# MCU103A_AltRouting_Misc.net
KiCad netlist of a schematic drawn in Altium Designer
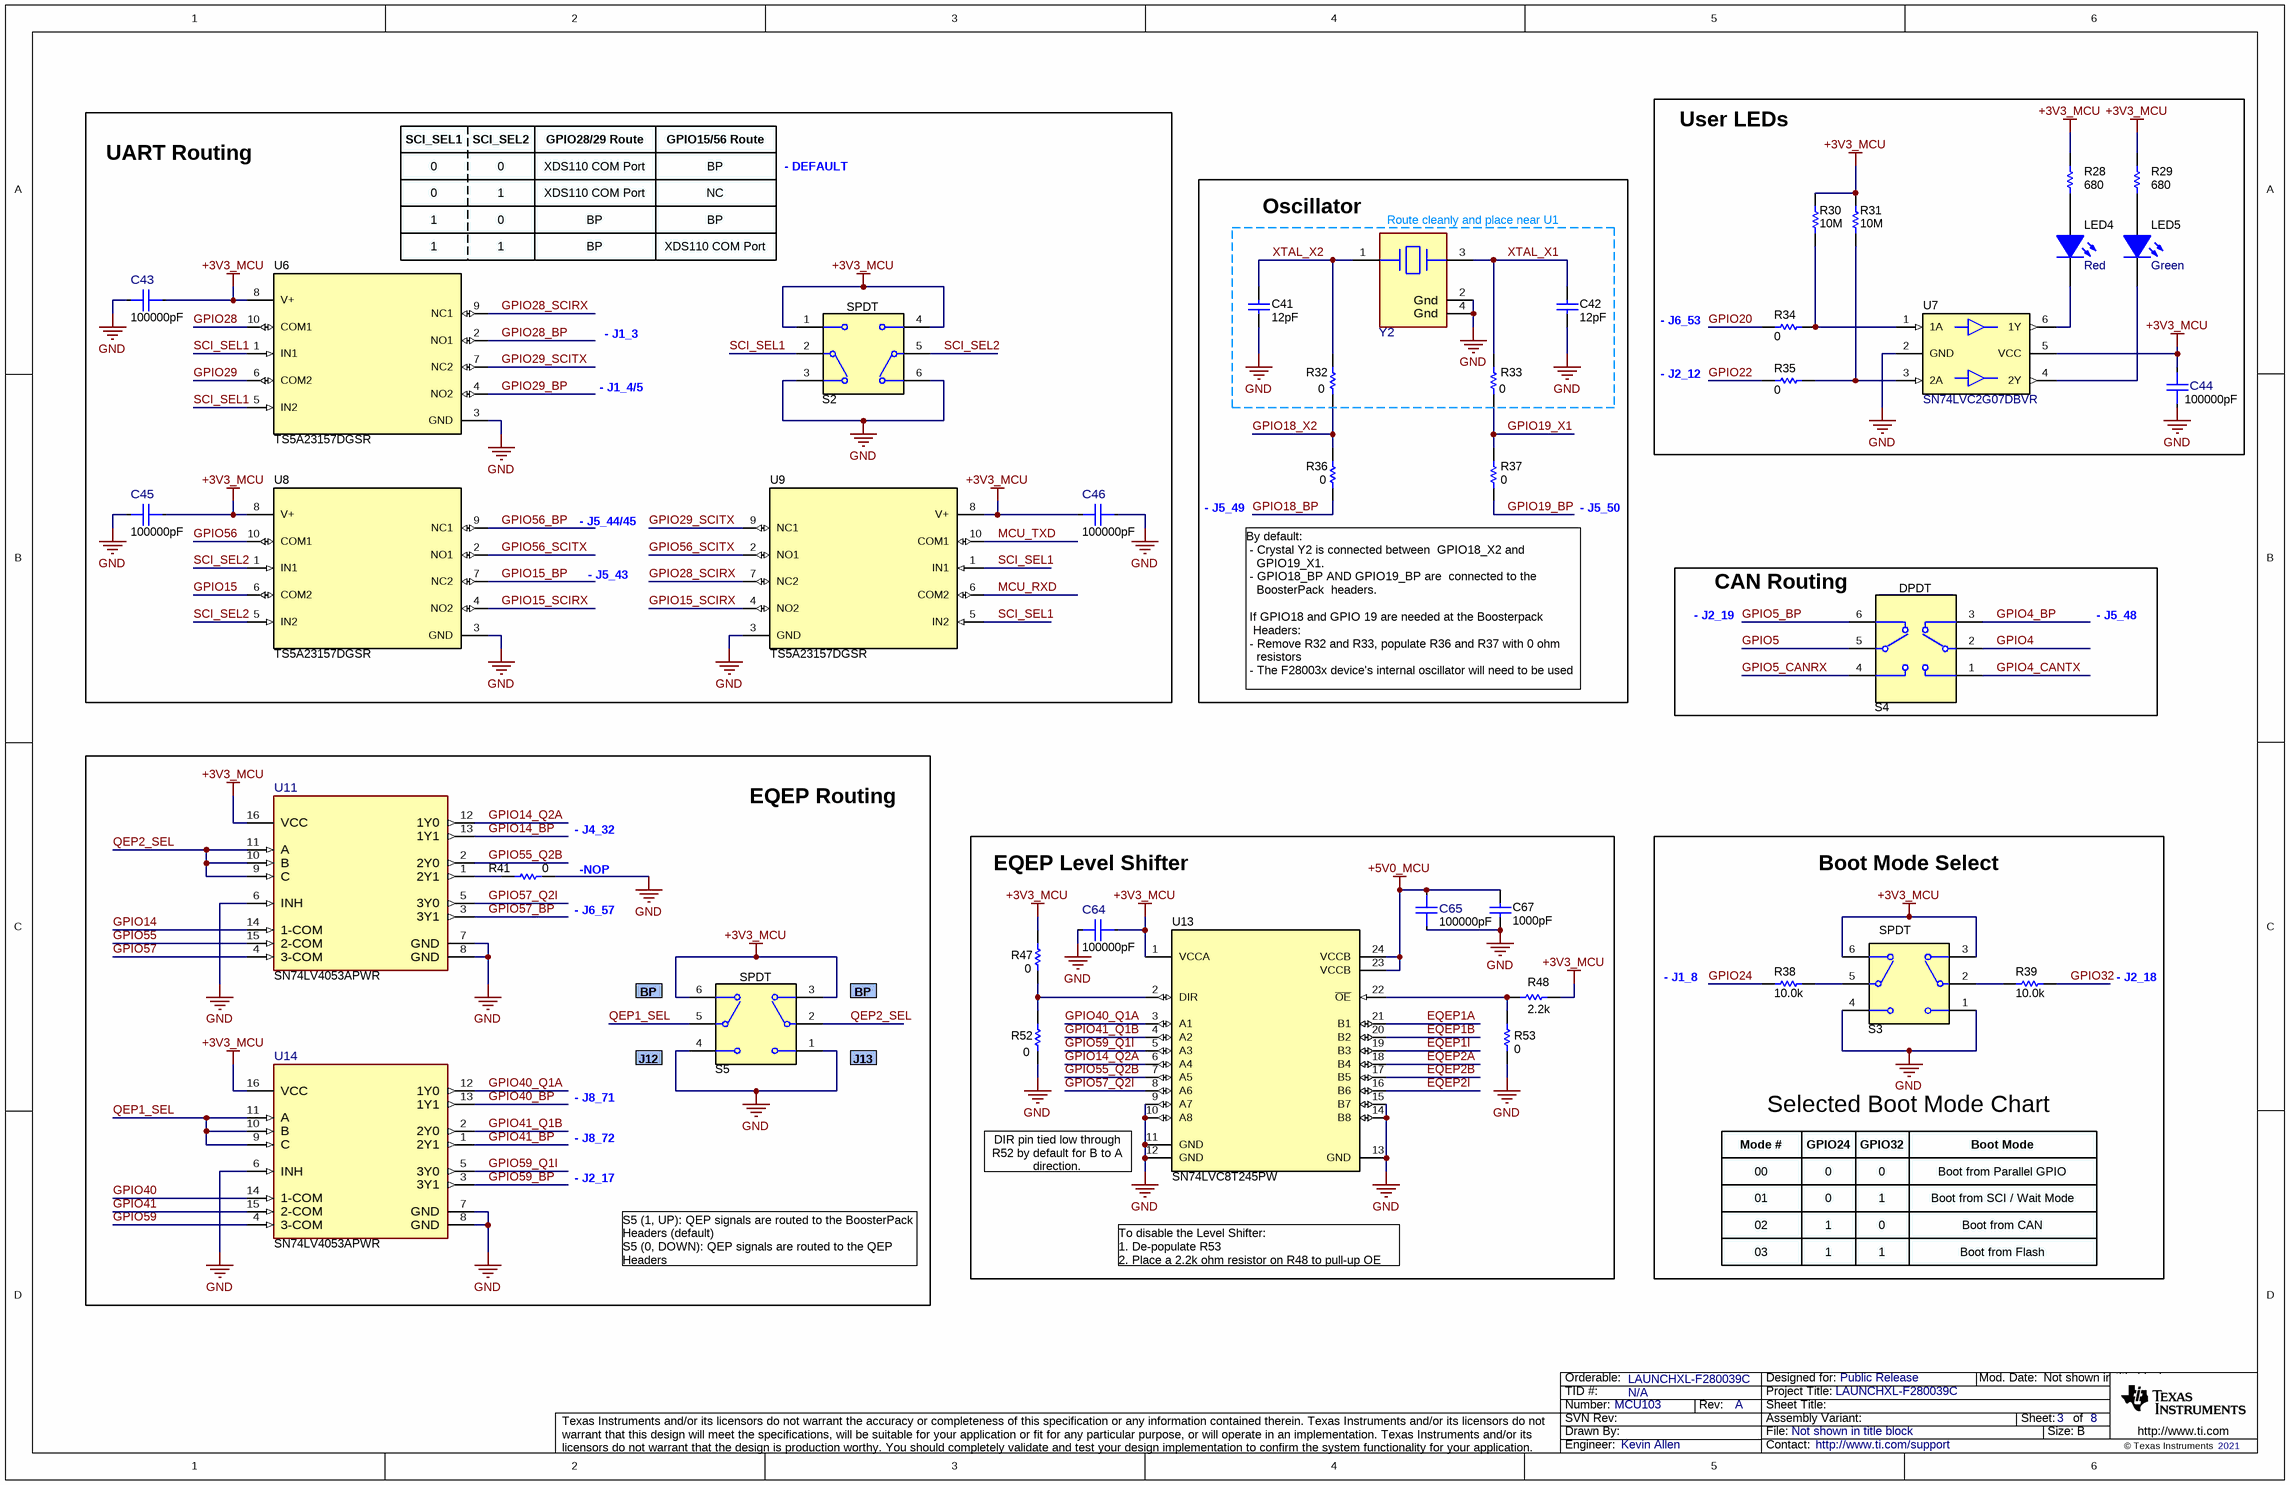
[diagram p0: MCU103A_AltRouting_Misc.SchDoc]

(export (version "E")
  (design (tool "Eeschema 10.0.6"))
  (components
    (comp (ref "C41")
      (value "C0402C120J3GACAUTO")
      (footprint "0402")
      (description "CAP, CERM, 12 pF, 25 V, +/- 5%, C0G/NP0, AEC-Q200 Grade 1, 0402")
      (fields
        (field (name "MANUFACTURER") "Kemet")
        (field (name "VALUEDISPLAYED") "12pF")
        (field (name "PUBLISHER") "Texas Instruments")
      )
      (libsource (lib "Altium Vault - TI") (part "Capacitor"))
    )
    (comp (ref "C42")
      (value "C0402C120J3GACAUTO")
      (footprint "0402")
      (description "CAP, CERM, 12 pF, 25 V, +/- 5%, C0G/NP0, AEC-Q200 Grade 1, 0402")
      (fields
        (field (name "MANUFACTURER") "Kemet")
        (field (name "VALUEDISPLAYED") "12pF")
        (field (name "PUBLISHER") "Texas Instruments")
      )
      (libsource (lib "Altium Vault - TI") (part "Capacitor"))
    )
    (comp (ref "C43")
      (value "885012205018")
      (footprint "FP-885012205018_0402-MFG")
      (description "0.1µF ±10% 10V Ceramic Capacitor X7R 0402 (1005 Metric)")
      (fields
        (field (name "MANUFACTURER") "Wurth Electronics")
        (field (name "MOUSER PART NUMBER") "710-885012205018")
        (field (name "VALUEDISPLAYED") "100000pF")
      )
      (libsource (lib "Altium Vault - TI") (part "SYM-885012205018"))
    )
    (comp (ref "C44")
      (value "885012205018")
      (footprint "FP-885012205018_0402-MFG")
      (description "0.1µF ±10% 10V Ceramic Capacitor X7R 0402 (1005 Metric)")
      (fields
        (field (name "MANUFACTURER") "Wurth Electronics")
        (field (name "MOUSER PART NUMBER") "710-885012205018")
        (field (name "VALUEDISPLAYED") "100000pF")
      )
      (libsource (lib "Altium Vault - TI") (part "SYM-885012205018"))
    )
    (comp (ref "C45")
      (value "885012205018")
      (footprint "FP-885012205018_0402-MFG")
      (description "0.1µF ±10% 10V Ceramic Capacitor X7R 0402 (1005 Metric)")
      (fields
        (field (name "MANUFACTURER") "Wurth Electronics")
        (field (name "MOUSER PART NUMBER") "710-885012205018")
        (field (name "VALUEDISPLAYED") "100000pF")
      )
      (libsource (lib "Altium Vault - TI") (part "SYM-885012205018"))
    )
    (comp (ref "C46")
      (value "885012205018")
      (footprint "FP-885012205018_0402-MFG")
      (description "0.1µF ±10% 10V Ceramic Capacitor X7R 0402 (1005 Metric)")
      (fields
        (field (name "MANUFACTURER") "Wurth Electronics")
        (field (name "MOUSER PART NUMBER") "710-885012205018")
        (field (name "VALUEDISPLAYED") "100000pF")
      )
      (libsource (lib "Altium Vault - TI") (part "SYM-885012205018"))
    )
    (comp (ref "C64")
      (value "885012205018")
      (footprint "FP-885012205018_0402-MFG")
      (description "0.1µF ±10% 10V Ceramic Capacitor X7R 0402 (1005 Metric)")
      (fields
        (field (name "MANUFACTURER") "Wurth Electronics")
        (field (name "MOUSER PART NUMBER") "710-885012205018")
        (field (name "VALUEDISPLAYED") "100000pF")
      )
      (libsource (lib "Altium Vault - TI") (part "SYM-885012205018"))
    )
    (comp (ref "C65")
      (value "885012205018")
      (footprint "FP-885012205018_0402-MFG")
      (description "0.1µF ±10% 10V Ceramic Capacitor X7R 0402 (1005 Metric)")
      (fields
        (field (name "MANUFACTURER") "Wurth Electronics")
        (field (name "MOUSER PART NUMBER") "710-885012205018")
        (field (name "VALUEDISPLAYED") "100000pF")
      )
      (libsource (lib "Altium Vault - TI") (part "SYM-885012205018"))
    )
    (comp (ref "C67")
      (value "885012205061")
      (footprint "0402")
      (description "CAP, CERM, 1000 pF, 50 V, +/- 10%, X7R, 0402")
      (fields
        (field (name "VALUEDISPLAYED") "1000pF")
        (field (name "MANUFACTURER") "Wurth Elektronik")
        (field (name "PUBLISHER") "Texas Instruments")
      )
      (libsource (lib "Altium Vault - TI") (part "Capacitor"))
    )
    (comp (ref "LED4")
      (value "Red")
      (footprint "WL-SMCW_RED_0805")
      (description "LED, Red, SMD")
      (fields (field (name "MANUFACTURER") "Wurth Elektronik") (field (name "PARTNUMBER") "150080SS75000"))
      (libsource (lib "Altium Vault - TI") (part "LED_A2_K1"))
    )
    (comp (ref "LED5")
      (value "Green")
      (footprint "LED_LTST-C171")
      (description "LED, Green, SMD")
      (fields (field (name "MANUFACTURER") "Lite-On") (field (name "PARTNUMBER") "LTST-C171GKT"))
      (libsource (lib "Altium Vault - TI") (part "LED"))
    )
    (comp (ref "R28")
      (value "CRCW0402680RJNED")
      (footprint "0402")
      (description "RES, 680, 5%, 0.063 W, AEC-Q200 Grade 0, 0402")
      (fields (field (name "MANUFACTURER") "Vishay-Dale") (field (name "VALUEDISPLAYED") "680"))
      (libsource (lib "Altium Vault - TI") (part "Resistor"))
    )
    (comp (ref "R29")
      (value "CRCW0402680RJNED")
      (footprint "0402")
      (description "RES, 680, 5%, 0.063 W, AEC-Q200 Grade 0, 0402")
      (fields (field (name "MANUFACTURER") "Vishay-Dale") (field (name "VALUEDISPLAYED") "680"))
      (libsource (lib "Altium Vault - TI") (part "Resistor"))
    )
    (comp (ref "R30")
      (value "CRCW040210M0JNED")
      (footprint "0402")
      (description "RES, 10 M, 5%, 0.063 W, AEC-Q200 Grade 0, 0402")
      (fields (field (name "VALUEDISPLAYED") "10M") (field (name "MANUFACTURER") "Vishay-Dale"))
      (libsource (lib "Altium Vault - TI") (part "Resistor"))
    )
    (comp (ref "R31")
      (value "CRCW040210M0JNED")
      (footprint "0402")
      (description "RES, 10 M, 5%, 0.063 W, AEC-Q200 Grade 0, 0402")
      (fields (field (name "VALUEDISPLAYED") "10M") (field (name "MANUFACTURER") "Vishay-Dale"))
      (libsource (lib "Altium Vault - TI") (part "Resistor"))
    )
    (comp (ref "R32")
      (value "CRCW06030000Z0EA")
      (footprint "0603")
      (description "RES, 0, 5%, 0.1 W, AEC-Q200 Grade 0, 0603")
      (fields (field (name "VALUEDISPLAYED") "0") (field (name "MANUFACTURER") "Vishay-Dale"))
      (libsource (lib "Altium Vault - TI") (part "Resistor"))
    )
    (comp (ref "R33")
      (value "CRCW06030000Z0EA")
      (footprint "0603")
      (description "RES, 0, 5%, 0.1 W, AEC-Q200 Grade 0, 0603")
      (fields (field (name "VALUEDISPLAYED") "0") (field (name "MANUFACTURER") "Vishay-Dale"))
      (libsource (lib "Altium Vault - TI") (part "Resistor"))
    )
    (comp (ref "R34")
      (value "CRCW06030000Z0EA")
      (footprint "0603")
      (description "RES, 0, 5%, 0.1 W, AEC-Q200 Grade 0, 0603")
      (fields (field (name "VALUEDISPLAYED") "0") (field (name "MANUFACTURER") "Vishay-Dale"))
      (libsource (lib "Altium Vault - TI") (part "Resistor"))
    )
    (comp (ref "R35")
      (value "CRCW06030000Z0EA")
      (footprint "0603")
      (description "RES, 0, 5%, 0.1 W, AEC-Q200 Grade 0, 0603")
      (fields (field (name "VALUEDISPLAYED") "0") (field (name "MANUFACTURER") "Vishay-Dale"))
      (libsource (lib "Altium Vault - TI") (part "Resistor"))
    )
    (comp (ref "R36")
      (value "CRCW06030000Z0EA")
      (footprint "0603")
      (description "RES, 0, 5%, 0.1 W, AEC-Q200 Grade 0, 0603")
      (fields (field (name "VALUEDISPLAYED") "0") (field (name "MANUFACTURER") "Vishay-Dale"))
      (libsource (lib "") (part "Resistor_1"))
    )
    (comp (ref "R37")
      (value "CRCW06030000Z0EA")
      (footprint "0603")
      (description "RES, 0, 5%, 0.1 W, AEC-Q200 Grade 0, 0603")
      (fields (field (name "VALUEDISPLAYED") "0") (field (name "MANUFACTURER") "Vishay-Dale"))
      (libsource (lib "Altium Vault - TI") (part "Resistor"))
    )
    (comp (ref "R38")
      (value "RC0603FR-0710KL")
      (footprint "0603")
      (description "RES, 10.0 k, 1%, 0.1 W, 0603")
      (fields (field (name "MANUFACTURER") "Yageo") (field (name "VALUEDISPLAYED") "10.0k"))
      (libsource (lib "Altium Vault - TI") (part "Resistor"))
    )
    (comp (ref "R39")
      (value "RC0603FR-0710KL")
      (footprint "0603")
      (description "RES, 10.0 k, 1%, 0.1 W, 0603")
      (fields (field (name "MANUFACTURER") "Yageo") (field (name "VALUEDISPLAYED") "10.0k"))
      (libsource (lib "Altium Vault - TI") (part "Resistor"))
    )
    (comp (ref "R41")
      (value "CRCW06030000Z0EA")
      (footprint "0603")
      (description "RES, 0, 5%, 0.1 W, AEC-Q200 Grade 0, 0603")
      (fields (field (name "VALUEDISPLAYED") "0") (field (name "MANUFACTURER") "Vishay-Dale"))
      (libsource (lib "Altium Vault - TI") (part "Resistor"))
    )
    (comp (ref "R47")
      (value "CRCW06030000Z0EA")
      (footprint "0603")
      (description "RES, 0, 5%, 0.1 W, AEC-Q200 Grade 0, 0603")
      (fields (field (name "VALUEDISPLAYED") "0") (field (name "MANUFACTURER") "Vishay-Dale"))
      (libsource (lib "Altium Vault - TI") (part "Resistor"))
    )
    (comp (ref "R48")
      (value "CRCW06032K20JNEA")
      (footprint "0603")
      (description "RES, 2.2 k, 5%, 0.1 W, AEC-Q200 Grade 0, 0603")
      (fields (field (name "VALUEDISPLAYED") "2.2k") (field (name "MANUFACTURER") "Vishay-Dale"))
      (libsource (lib "Altium Vault - TI") (part "Resistor"))
    )
    (comp (ref "R52")
      (value "CRCW06030000Z0EA")
      (footprint "0603")
      (description "RES, 0, 5%, 0.1 W, AEC-Q200 Grade 0, 0603")
      (fields (field (name "VALUEDISPLAYED") "0") (field (name "MANUFACTURER") "Vishay-Dale"))
      (libsource (lib "Altium Vault - TI") (part "Resistor"))
    )
    (comp (ref "R53")
      (value "CRCW06030000Z0EA")
      (footprint "0603")
      (description "RES, 0, 5%, 0.1 W, AEC-Q200 Grade 0, 0603")
      (fields (field (name "VALUEDISPLAYED") "0") (field (name "MANUFACTURER") "Vishay-Dale"))
      (libsource (lib "Altium Vault - TI") (part "Resistor"))
    )
    (comp (ref "S2")
      (value "CAS-D20TA")
      (footprint "SW_CAS-D20TA")
      (description "Switch, Dual SPDT,  2 Pos, 0.1A, 6VDC, SMD")
      (fields
        (field (name "MANUFACTURER") "Copal Electronics")
        (field (name "PUBLISHER") "Texas Instruments")
      )
      (libsource (lib "") (part "SW_SPDT_CAS-D20TA_1"))
    )
    (comp (ref "S3")
      (value "CAS-D20TA")
      (footprint "SW_CAS-D20TA")
      (description "Switch, Dual SPDT,  2 Pos, 0.1A, 6VDC, SMD")
      (fields
        (field (name "MANUFACTURER") "Copal Electronics")
        (field (name "PUBLISHER") "Texas Instruments")
      )
      (libsource (lib "Altium Vault - TI") (part "SW_SPDT_CAS-D20TA"))
    )
    (comp (ref "S4")
      (value "CAS-220TA")
      (footprint "SW_CAS-220TA")
      (description "SLIDE SWITCH DPDT  .1A, SMT")
      (fields
        (field (name "MANUFACTURER") "Copal Electronics")
        (field (name "PUBLISHER") "Texas Instruments")
      )
      (libsource (lib "Altium Vault - TI") (part "SW_CAS-220TA"))
    )
    (comp (ref "S5")
      (value "CAS-D20TA")
      (footprint "SW_CAS-D20TA")
      (description "Switch, Dual SPDT,  2 Pos, 0.1A, 6VDC, SMD")
      (fields
        (field (name "MANUFACTURER") "Copal Electronics")
        (field (name "PUBLISHER") "Texas Instruments")
      )
      (libsource (lib "Altium Vault - TI") (part "SW_SPDT_CAS-D20TA"))
    )
    (comp (ref "U6")
      (value "TS5A23157DGSR")
      (footprint "DGS0010A_N")
      (description "DUAL 10-Ohm SPDT ANALOG SWITCH, DGS0010A (VSSOP-10)")
      (fields
        (field (name "ALTERNATE PARTNUMBER") "TS5A23157DGST")
        (field (name "MANUFACTURER") "Texas Instruments")
        (field (name "PARTNUMBER") "TS5A23157DGSR")
        (field (name "PUBLISHER") "Texas Instruments")
      )
      (libsource (lib "Altium Vault - TI") (part "TS5A23159"))
    )
    (comp (ref "U7")
      (value "SN74LVC2G07DBVR")
      (footprint "DBV0006A_N")
      (description "Dual Buffer/Driver with Open-Drain Output, DBV0006A, LARGE T&R")
      (fields
        (field (name "GENERIC PART NUMBER") "SN74LVC2G07")
        (field (name "MANUFACTURER") "Texas Instruments")
      )
      (libsource (lib "Altium Vault - TI") (part "SN74LVC2G07"))
    )
    (comp (ref "U8")
      (value "TS5A23157DGSR")
      (footprint "DGS0010A_N")
      (description "DUAL 10-Ohm SPDT ANALOG SWITCH, DGS0010A (VSSOP-10)")
      (fields
        (field (name "ALTERNATE PARTNUMBER") "TS5A23157DGST")
        (field (name "MANUFACTURER") "Texas Instruments")
        (field (name "PARTNUMBER") "TS5A23157DGSR")
        (field (name "PUBLISHER") "Texas Instruments")
      )
      (libsource (lib "Altium Vault - TI") (part "TS5A23159"))
    )
    (comp (ref "U9")
      (value "TS5A23157DGSR")
      (footprint "DGS0010A_N")
      (description "DUAL 10-Ohm SPDT ANALOG SWITCH, DGS0010A (VSSOP-10)")
      (fields
        (field (name "ALTERNATE PARTNUMBER") "TS5A23157DGST")
        (field (name "MANUFACTURER") "Texas Instruments")
        (field (name "PARTNUMBER") "TS5A23157DGSR")
        (field (name "PUBLISHER") "Texas Instruments")
      )
      (libsource (lib "") (part "TS5A23159_1"))
    )
    (comp (ref "U11")
      (value "SN74LV4053APWR")
      (footprint "PW0016A-MFG")
      (description "3 Circuit IC Switch 2:1 75Ohm 16-TSSOP")
      (fields
        (field (name "PARTNUMBER") "SN74LV4053APWR")
        (field (name "MOUSER PART NUMBER") "595-SN74LV4053APWR")
        (field (name "DIGIKEY PART NUMBER") "296-3833-1-ND")
      )
      (libsource (lib "Altium Vault - TI") (part "SYM-SN74LV4053APWR"))
    )
    (comp (ref "U13")
      (value "SN74LVC8T245PW")
      (footprint "PW0024A_N")
      (fields (field (name "MANUFACTURER") "Texas Instruments") (field (name "PARTNUMBER") "SN74LVC8T245PW"))
      (libsource (lib "Altium Vault - TI") (part "SN74LVC8T245"))
    )
    (comp (ref "U14")
      (value "SN74LV4053APWR")
      (footprint "PW0016A-MFG")
      (description "3 Circuit IC Switch 2:1 75Ohm 16-TSSOP")
      (fields
        (field (name "PARTNUMBER") "SN74LV4053APWR")
        (field (name "MOUSER PART NUMBER") "595-SN74LV4053APWR")
        (field (name "DIGIKEY PART NUMBER") "296-3833-1-ND")
      )
      (libsource (lib "Altium Vault - TI") (part "SYM-SN74LV4053APWR"))
    )
    (comp (ref "Y2")
      (value "ECS-200-8-30B-CKM")
      (footprint "FP-ECS-200-8-30B-CKM_SMD4-MFG")
      (description "20 MHz ±10ppm Crystal 8pF 40 Ohms 4-SMD, No Lead")
      (fields
        (field (name "MOUSER PART NUMBER") "520-200-8-30B-CKM")
        (field (name "MANUFACTURER") "ECS International")
      )
      (libsource (lib "Altium Vault - TI") (part "SYM-ECS-200-8-30B-CKM"))
    )
  )
  (nets
    (net (code "1") (name "+3V3_MCU") (class "Default")
      (node (ref "C43") (pin "1") (pinfunction "1_1") (pintype "passive"))
      (node (ref "C44") (pin "2") (pinfunction "2_2") (pintype "passive"))
      (node (ref "C45") (pin "1") (pinfunction "1_1") (pintype "passive"))
      (node (ref "C46") (pin "2") (pinfunction "2_2") (pintype "passive"))
      (node (ref "C64") (pin "1") (pinfunction "1_1") (pintype "passive"))
      (node (ref "R28") (pin "2") (pinfunction "2_2") (pintype "passive"))
      (node (ref "R29") (pin "2") (pinfunction "2_2") (pintype "passive"))
      (node (ref "R30") (pin "2") (pinfunction "2_2") (pintype "passive"))
      (node (ref "R31") (pin "2") (pinfunction "2_2") (pintype "passive"))
      (node (ref "R47") (pin "2") (pinfunction "2_2") (pintype "passive"))
      (node (ref "R48") (pin "2") (pinfunction "2_2") (pintype "passive"))
      (node (ref "S2") (pin "1") (pinfunction "1_1") (pintype "passive"))
      (node (ref "S2") (pin "4") (pinfunction "4_4") (pintype "passive"))
      (node (ref "S3") (pin "3") (pinfunction "3_3") (pintype "passive"))
      (node (ref "S3") (pin "6") (pinfunction "6_6") (pintype "passive"))
      (node (ref "S5") (pin "3") (pinfunction "3_3") (pintype "passive"))
      (node (ref "S5") (pin "6") (pinfunction "6_6") (pintype "passive"))
      (node (ref "U11") (pin "16") (pinfunction "VCC_16") (pintype "power_in"))
      (node (ref "U13") (pin "1") (pinfunction "VCCA_1") (pintype "power_in"))
      (node (ref "U14") (pin "16") (pinfunction "VCC_16") (pintype "power_in"))
      (node (ref "U6") (pin "8") (pinfunction "V+_8") (pintype "power_in"))
      (node (ref "U7") (pin "5") (pinfunction "VCC_5") (pintype "power_in"))
      (node (ref "U8") (pin "8") (pinfunction "V+_8") (pintype "power_in"))
      (node (ref "U9") (pin "8") (pinfunction "V+_8") (pintype "power_in"))
    )
    (net (code "2") (name "+5V0_MCU") (class "Default")
      (node (ref "C65") (pin "2") (pinfunction "2_2") (pintype "passive"))
      (node (ref "C67") (pin "1") (pinfunction "1_1") (pintype "passive"))
      (node (ref "U13") (pin "23") (pinfunction "VCCB_23") (pintype "power_in"))
      (node (ref "U13") (pin "24") (pinfunction "VCCB_24") (pintype "power_in"))
    )
    (net (code "3") (name "/EQEP1A") (class "Default")
      (node (ref "U13") (pin "21") (pinfunction "B1_21") (pintype "bidirectional"))
    )
    (net (code "4") (name "/EQEP1B") (class "Default")
      (node (ref "U13") (pin "20") (pinfunction "B2_20") (pintype "bidirectional"))
    )
    (net (code "5") (name "/EQEP1I") (class "Default")
      (node (ref "U13") (pin "19") (pinfunction "B3_19") (pintype "bidirectional"))
    )
    (net (code "6") (name "/EQEP2A") (class "Default")
      (node (ref "U13") (pin "18") (pinfunction "B4_18") (pintype "bidirectional"))
    )
    (net (code "7") (name "/EQEP2B") (class "Default")
      (node (ref "U13") (pin "17") (pinfunction "B5_17") (pintype "bidirectional"))
    )
    (net (code "8") (name "/EQEP2I") (class "Default")
      (node (ref "U13") (pin "16") (pinfunction "B6_16") (pintype "bidirectional"))
    )
    (net (code "9") (name "/GPIO4") (class "Default")
      (node (ref "S4") (pin "2") (pinfunction "2_2") (pintype "passive"))
    )
    (net (code "10") (name "/GPIO4_BP") (class "Default")
      (node (ref "S4") (pin "3") (pinfunction "3_3") (pintype "passive"))
    )
    (net (code "11") (name "/GPIO4_CANTX") (class "Default")
      (node (ref "S4") (pin "1") (pinfunction "1_1") (pintype "passive"))
    )
    (net (code "12") (name "/GPIO5") (class "Default")
      (node (ref "S4") (pin "5") (pinfunction "5_5") (pintype "passive"))
    )
    (net (code "13") (name "/GPIO5_BP") (class "Default")
      (node (ref "S4") (pin "6") (pinfunction "6_6") (pintype "passive"))
    )
    (net (code "14") (name "/GPIO5_CANRX") (class "Default")
      (node (ref "S4") (pin "4") (pinfunction "4_4") (pintype "passive"))
    )
    (net (code "15") (name "/GPIO14") (class "Default")
      (node (ref "U11") (pin "14") (pinfunction "1-COM_14") (pintype "input"))
    )
    (net (code "16") (name "/GPIO14_BP") (class "Default")
      (node (ref "U11") (pin "13") (pinfunction "1Y1_13") (pintype "output"))
    )
    (net (code "17") (name "/GPIO14_Q2A") (class "Default")
      (node (ref "U11") (pin "12") (pinfunction "1Y0_12") (pintype "output"))
      (node (ref "U13") (pin "6") (pinfunction "A4_6") (pintype "bidirectional"))
    )
    (net (code "18") (name "/GPIO15") (class "Default")
      (node (ref "U8") (pin "6") (pinfunction "COM2_6") (pintype "bidirectional"))
    )
    (net (code "19") (name "/GPIO15_BP") (class "Default")
      (node (ref "U8") (pin "7") (pinfunction "NC2_7") (pintype "bidirectional"))
    )
    (net (code "20") (name "/GPIO15_SCIRX") (class "Default")
      (node (ref "U8") (pin "4") (pinfunction "NO2_4") (pintype "bidirectional"))
      (node (ref "U9") (pin "4") (pinfunction "NO2_4") (pintype "bidirectional"))
    )
    (net (code "21") (name "/GPIO18_BP") (class "Default")
      (node (ref "R36") (pin "1") (pinfunction "1_1") (pintype "passive"))
    )
    (net (code "22") (name "/GPIO18_X2") (class "Default")
      (node (ref "R32") (pin "1") (pinfunction "1_1") (pintype "passive"))
      (node (ref "R36") (pin "2") (pinfunction "2_2") (pintype "passive"))
    )
    (net (code "23") (name "/GPIO19_BP") (class "Default")
      (node (ref "R37") (pin "1") (pinfunction "1_1") (pintype "passive"))
    )
    (net (code "24") (name "/GPIO19_X1") (class "Default")
      (node (ref "R33") (pin "1") (pinfunction "1_1") (pintype "passive"))
      (node (ref "R37") (pin "2") (pinfunction "2_2") (pintype "passive"))
    )
    (net (code "25") (name "/GPIO20") (class "Default")
      (node (ref "R34") (pin "1") (pinfunction "1_1") (pintype "passive"))
    )
    (net (code "26") (name "/GPIO22") (class "Default")
      (node (ref "R35") (pin "1") (pinfunction "1_1") (pintype "passive"))
    )
    (net (code "27") (name "/GPIO24") (class "Default")
      (node (ref "R38") (pin "1") (pinfunction "1_1") (pintype "passive"))
    )
    (net (code "28") (name "/GPIO28") (class "Default")
      (node (ref "U6") (pin "10") (pinfunction "COM1_10") (pintype "bidirectional"))
    )
    (net (code "29") (name "/GPIO28_BP") (class "Default")
      (node (ref "U6") (pin "2") (pinfunction "NO1_2") (pintype "bidirectional"))
    )
    (net (code "30") (name "/GPIO28_SCIRX") (class "Default")
      (node (ref "U6") (pin "9") (pinfunction "NC1_9") (pintype "bidirectional"))
      (node (ref "U9") (pin "7") (pinfunction "NC2_7") (pintype "bidirectional"))
    )
    (net (code "31") (name "/GPIO29") (class "Default")
      (node (ref "U6") (pin "6") (pinfunction "COM2_6") (pintype "bidirectional"))
    )
    (net (code "32") (name "/GPIO29_BP") (class "Default")
      (node (ref "U6") (pin "4") (pinfunction "NO2_4") (pintype "bidirectional"))
    )
    (net (code "33") (name "/GPIO29_SCITX") (class "Default")
      (node (ref "U6") (pin "7") (pinfunction "NC2_7") (pintype "bidirectional"))
      (node (ref "U9") (pin "9") (pinfunction "NC1_9") (pintype "bidirectional"))
    )
    (net (code "34") (name "/GPIO32") (class "Default")
      (node (ref "R39") (pin "2") (pinfunction "2_2") (pintype "passive"))
    )
    (net (code "35") (name "/GPIO40") (class "Default")
      (node (ref "U14") (pin "14") (pinfunction "1-COM_14") (pintype "input"))
    )
    (net (code "36") (name "/GPIO40_BP") (class "Default")
      (node (ref "U14") (pin "13") (pinfunction "1Y1_13") (pintype "output"))
    )
    (net (code "37") (name "/GPIO40_Q1A") (class "Default")
      (node (ref "U13") (pin "3") (pinfunction "A1_3") (pintype "bidirectional"))
      (node (ref "U14") (pin "12") (pinfunction "1Y0_12") (pintype "output"))
    )
    (net (code "38") (name "/GPIO41") (class "Default")
      (node (ref "U14") (pin "15") (pinfunction "2-COM_15") (pintype "input"))
    )
    (net (code "39") (name "/GPIO41_BP") (class "Default")
      (node (ref "U14") (pin "1") (pinfunction "2Y1_1") (pintype "output"))
    )
    (net (code "40") (name "/GPIO41_Q1B") (class "Default")
      (node (ref "U13") (pin "4") (pinfunction "A2_4") (pintype "bidirectional"))
      (node (ref "U14") (pin "2") (pinfunction "2Y0_2") (pintype "output"))
    )
    (net (code "41") (name "/GPIO55") (class "Default")
      (node (ref "U11") (pin "15") (pinfunction "2-COM_15") (pintype "input"))
    )
    (net (code "42") (name "/GPIO55_Q2B") (class "Default")
      (node (ref "U11") (pin "2") (pinfunction "2Y0_2") (pintype "output"))
      (node (ref "U13") (pin "7") (pinfunction "A5_7") (pintype "bidirectional"))
    )
    (net (code "43") (name "/GPIO56") (class "Default")
      (node (ref "U8") (pin "10") (pinfunction "COM1_10") (pintype "bidirectional"))
    )
    (net (code "44") (name "/GPIO56_BP") (class "Default")
      (node (ref "U8") (pin "9") (pinfunction "NC1_9") (pintype "bidirectional"))
    )
    (net (code "45") (name "/GPIO56_SCITX") (class "Default")
      (node (ref "U8") (pin "2") (pinfunction "NO1_2") (pintype "bidirectional"))
      (node (ref "U9") (pin "2") (pinfunction "NO1_2") (pintype "bidirectional"))
    )
    (net (code "46") (name "/GPIO57") (class "Default")
      (node (ref "U11") (pin "4") (pinfunction "3-COM_4") (pintype "input"))
    )
    (net (code "47") (name "/GPIO57_BP") (class "Default")
      (node (ref "U11") (pin "3") (pinfunction "3Y1_3") (pintype "output"))
    )
    (net (code "48") (name "/GPIO57_Q2I") (class "Default")
      (node (ref "U11") (pin "5") (pinfunction "3Y0_5") (pintype "output"))
      (node (ref "U13") (pin "8") (pinfunction "A6_8") (pintype "bidirectional"))
    )
    (net (code "49") (name "/GPIO59") (class "Default")
      (node (ref "U14") (pin "4") (pinfunction "3-COM_4") (pintype "input"))
    )
    (net (code "50") (name "/GPIO59_BP") (class "Default")
      (node (ref "U14") (pin "3") (pinfunction "3Y1_3") (pintype "output"))
    )
    (net (code "51") (name "/GPIO59_Q1I") (class "Default")
      (node (ref "U13") (pin "5") (pinfunction "A3_5") (pintype "bidirectional"))
      (node (ref "U14") (pin "5") (pinfunction "3Y0_5") (pintype "output"))
    )
    (net (code "52") (name "/MCU_RXD") (class "Default")
      (node (ref "U9") (pin "6") (pinfunction "COM2_6") (pintype "bidirectional"))
    )
    (net (code "53") (name "/MCU_TXD") (class "Default")
      (node (ref "U9") (pin "10") (pinfunction "COM1_10") (pintype "bidirectional"))
    )
    (net (code "54") (name "/QEP1_SEL") (class "Default")
      (node (ref "S5") (pin "5") (pinfunction "C_5") (pintype "passive"))
      (node (ref "U14") (pin "10") (pinfunction "B_10") (pintype "input"))
      (node (ref "U14") (pin "11") (pinfunction "A_11") (pintype "input"))
      (node (ref "U14") (pin "9") (pinfunction "C_9") (pintype "input"))
    )
    (net (code "55") (name "/QEP2_SEL") (class "Default")
      (node (ref "S5") (pin "2") (pinfunction "C_2") (pintype "passive"))
      (node (ref "U11") (pin "10") (pinfunction "B_10") (pintype "input"))
      (node (ref "U11") (pin "11") (pinfunction "A_11") (pintype "input"))
      (node (ref "U11") (pin "9") (pinfunction "C_9") (pintype "input"))
    )
    (net (code "56") (name "/SCI_SEL1") (class "Default")
      (node (ref "S2") (pin "2") (pinfunction "C_2") (pintype "passive"))
      (node (ref "U6") (pin "1") (pinfunction "IN1_1") (pintype "input"))
      (node (ref "U6") (pin "5") (pinfunction "IN2_5") (pintype "input"))
      (node (ref "U9") (pin "1") (pinfunction "IN1_1") (pintype "input"))
      (node (ref "U9") (pin "5") (pinfunction "IN2_5") (pintype "input"))
    )
    (net (code "57") (name "/SCI_SEL2") (class "Default")
      (node (ref "S2") (pin "5") (pinfunction "C_5") (pintype "passive"))
      (node (ref "U8") (pin "1") (pinfunction "IN1_1") (pintype "input"))
      (node (ref "U8") (pin "5") (pinfunction "IN2_5") (pintype "input"))
    )
    (net (code "58") (name "/XTAL_X1") (class "Default")
      (node (ref "C42") (pin "1") (pinfunction "1_1") (pintype "passive"))
      (node (ref "R33") (pin "2") (pinfunction "2_2") (pintype "passive"))
      (node (ref "Y2") (pin "3") (pinfunction "Out/In_3") (pintype "passive"))
    )
    (net (code "59") (name "/XTAL_X2") (class "Default")
      (node (ref "C41") (pin "1") (pinfunction "1_1") (pintype "passive"))
      (node (ref "R32") (pin "2") (pinfunction "2_2") (pintype "passive"))
      (node (ref "Y2") (pin "1") (pinfunction "In/Out_1") (pintype "passive"))
    )
    (net (code "60") (name "GND") (class "Default")
      (node (ref "C41") (pin "2") (pinfunction "2_2") (pintype "passive"))
      (node (ref "C42") (pin "2") (pinfunction "2_2") (pintype "passive"))
      (node (ref "C43") (pin "2") (pinfunction "2_2") (pintype "passive"))
      (node (ref "C44") (pin "1") (pinfunction "1_1") (pintype "passive"))
      (node (ref "C45") (pin "2") (pinfunction "2_2") (pintype "passive"))
      (node (ref "C46") (pin "1") (pinfunction "1_1") (pintype "passive"))
      (node (ref "C64") (pin "2") (pinfunction "2_2") (pintype "passive"))
      (node (ref "C65") (pin "1") (pinfunction "1_1") (pintype "passive"))
      (node (ref "C67") (pin "2") (pinfunction "2_2") (pintype "passive"))
      (node (ref "R41") (pin "2") (pinfunction "2_2") (pintype "passive"))
      (node (ref "R52") (pin "1") (pinfunction "1_1") (pintype "passive"))
      (node (ref "R53") (pin "2") (pinfunction "2_2") (pintype "passive"))
      (node (ref "S2") (pin "3") (pinfunction "3_3") (pintype "passive"))
      (node (ref "S2") (pin "6") (pinfunction "6_6") (pintype "passive"))
      (node (ref "S3") (pin "1") (pinfunction "1_1") (pintype "passive"))
      (node (ref "S3") (pin "4") (pinfunction "4_4") (pintype "passive"))
      (node (ref "S5") (pin "1") (pinfunction "1_1") (pintype "passive"))
      (node (ref "S5") (pin "4") (pinfunction "4_4") (pintype "passive"))
      (node (ref "U11") (pin "6") (pinfunction "INH_6") (pintype "input"))
      (node (ref "U11") (pin "7") (pinfunction "GND_7") (pintype "power_in"))
      (node (ref "U11") (pin "8") (pinfunction "GND_8") (pintype "power_in"))
      (node (ref "U13") (pin "10") (pinfunction "A8_10") (pintype "bidirectional"))
      (node (ref "U13") (pin "11") (pinfunction "GND_11") (pintype "power_in"))
      (node (ref "U13") (pin "12") (pinfunction "GND_12") (pintype "power_in"))
      (node (ref "U13") (pin "13") (pinfunction "GND_13") (pintype "power_in"))
      (node (ref "U13") (pin "14") (pinfunction "B8_14") (pintype "bidirectional"))
      (node (ref "U13") (pin "15") (pinfunction "B7_15") (pintype "bidirectional"))
      (node (ref "U13") (pin "9") (pinfunction "A7_9") (pintype "bidirectional"))
      (node (ref "U14") (pin "6") (pinfunction "INH_6") (pintype "input"))
      (node (ref "U14") (pin "7") (pinfunction "GND_7") (pintype "power_in"))
      (node (ref "U14") (pin "8") (pinfunction "GND_8") (pintype "power_in"))
      (node (ref "U6") (pin "3") (pinfunction "GND_3") (pintype "power_in"))
      (node (ref "U7") (pin "2") (pinfunction "GND_2") (pintype "power_in"))
      (node (ref "U8") (pin "3") (pinfunction "GND_3") (pintype "power_in"))
      (node (ref "U9") (pin "3") (pinfunction "GND_3") (pintype "power_in"))
      (node (ref "Y2") (pin "2") (pinfunction "Gnd_2") (pintype "power_in"))
      (node (ref "Y2") (pin "4") (pinfunction "Gnd_4") (pintype "power_in"))
    )
    (net (code "61") (name "Net-(LED4-A)") (class "Default")
      (node (ref "LED4") (pin "2") (pinfunction "A_2") (pintype "passive"))
      (node (ref "R28") (pin "1") (pinfunction "1_1") (pintype "passive"))
    )
    (net (code "62") (name "Net-(LED4-K)") (class "Default")
      (node (ref "LED4") (pin "1") (pinfunction "K_1") (pintype "passive"))
      (node (ref "U7") (pin "6") (pinfunction "1Y_6") (pintype "output"))
    )
    (net (code "63") (name "Net-(LED5-A)") (class "Default")
      (node (ref "LED5") (pin "1") (pinfunction "A_1") (pintype "passive"))
      (node (ref "R29") (pin "1") (pinfunction "1_1") (pintype "passive"))
    )
    (net (code "64") (name "Net-(LED5-K)") (class "Default")
      (node (ref "LED5") (pin "2") (pinfunction "K_2") (pintype "passive"))
      (node (ref "U7") (pin "4") (pinfunction "2Y_4") (pintype "output"))
    )
    (net (code "65") (name "Net-(R38-Pad2)") (class "Default")
      (node (ref "R38") (pin "2") (pinfunction "2_2") (pintype "passive"))
      (node (ref "S3") (pin "5") (pinfunction "C_5") (pintype "passive"))
    )
    (net (code "66") (name "Net-(R39-Pad1)") (class "Default")
      (node (ref "R39") (pin "1") (pinfunction "1_1") (pintype "passive"))
      (node (ref "S3") (pin "2") (pinfunction "C_2") (pintype "passive"))
    )
    (net (code "67") (name "Net-(U7-1A)") (class "Default")
      (node (ref "R30") (pin "1") (pinfunction "1_1") (pintype "passive"))
      (node (ref "R34") (pin "2") (pinfunction "2_2") (pintype "passive"))
      (node (ref "U7") (pin "1") (pinfunction "1A_1") (pintype "input"))
    )
    (net (code "68") (name "Net-(U7-2A)") (class "Default")
      (node (ref "R31") (pin "1") (pinfunction "1_1") (pintype "passive"))
      (node (ref "R35") (pin "2") (pinfunction "2_2") (pintype "passive"))
      (node (ref "U7") (pin "3") (pinfunction "2A_3") (pintype "input"))
    )
    (net (code "69") (name "Net-(U11-2Y1)") (class "Default")
      (node (ref "R41") (pin "1") (pinfunction "1_1") (pintype "passive"))
      (node (ref "U11") (pin "1") (pinfunction "2Y1_1") (pintype "output"))
    )
    (net (code "70") (name "Net-(U13-DIR)") (class "Default")
      (node (ref "R47") (pin "1") (pinfunction "1_1") (pintype "passive"))
      (node (ref "R52") (pin "2") (pinfunction "2_2") (pintype "passive"))
      (node (ref "U13") (pin "2") (pinfunction "DIR_2") (pintype "bidirectional"))
    )
    (net (code "71") (name "Net-(U13-OE)") (class "Default")
      (node (ref "R48") (pin "1") (pinfunction "1_1") (pintype "passive"))
      (node (ref "R53") (pin "1") (pinfunction "1_1") (pintype "passive"))
      (node (ref "U13") (pin "22") (pinfunction "OE_22") (pintype "input"))
    )
  )
)
